# Solar_Charge_Controller_ver2.net
KiCad netlist of a schematic drawn in EAGLE
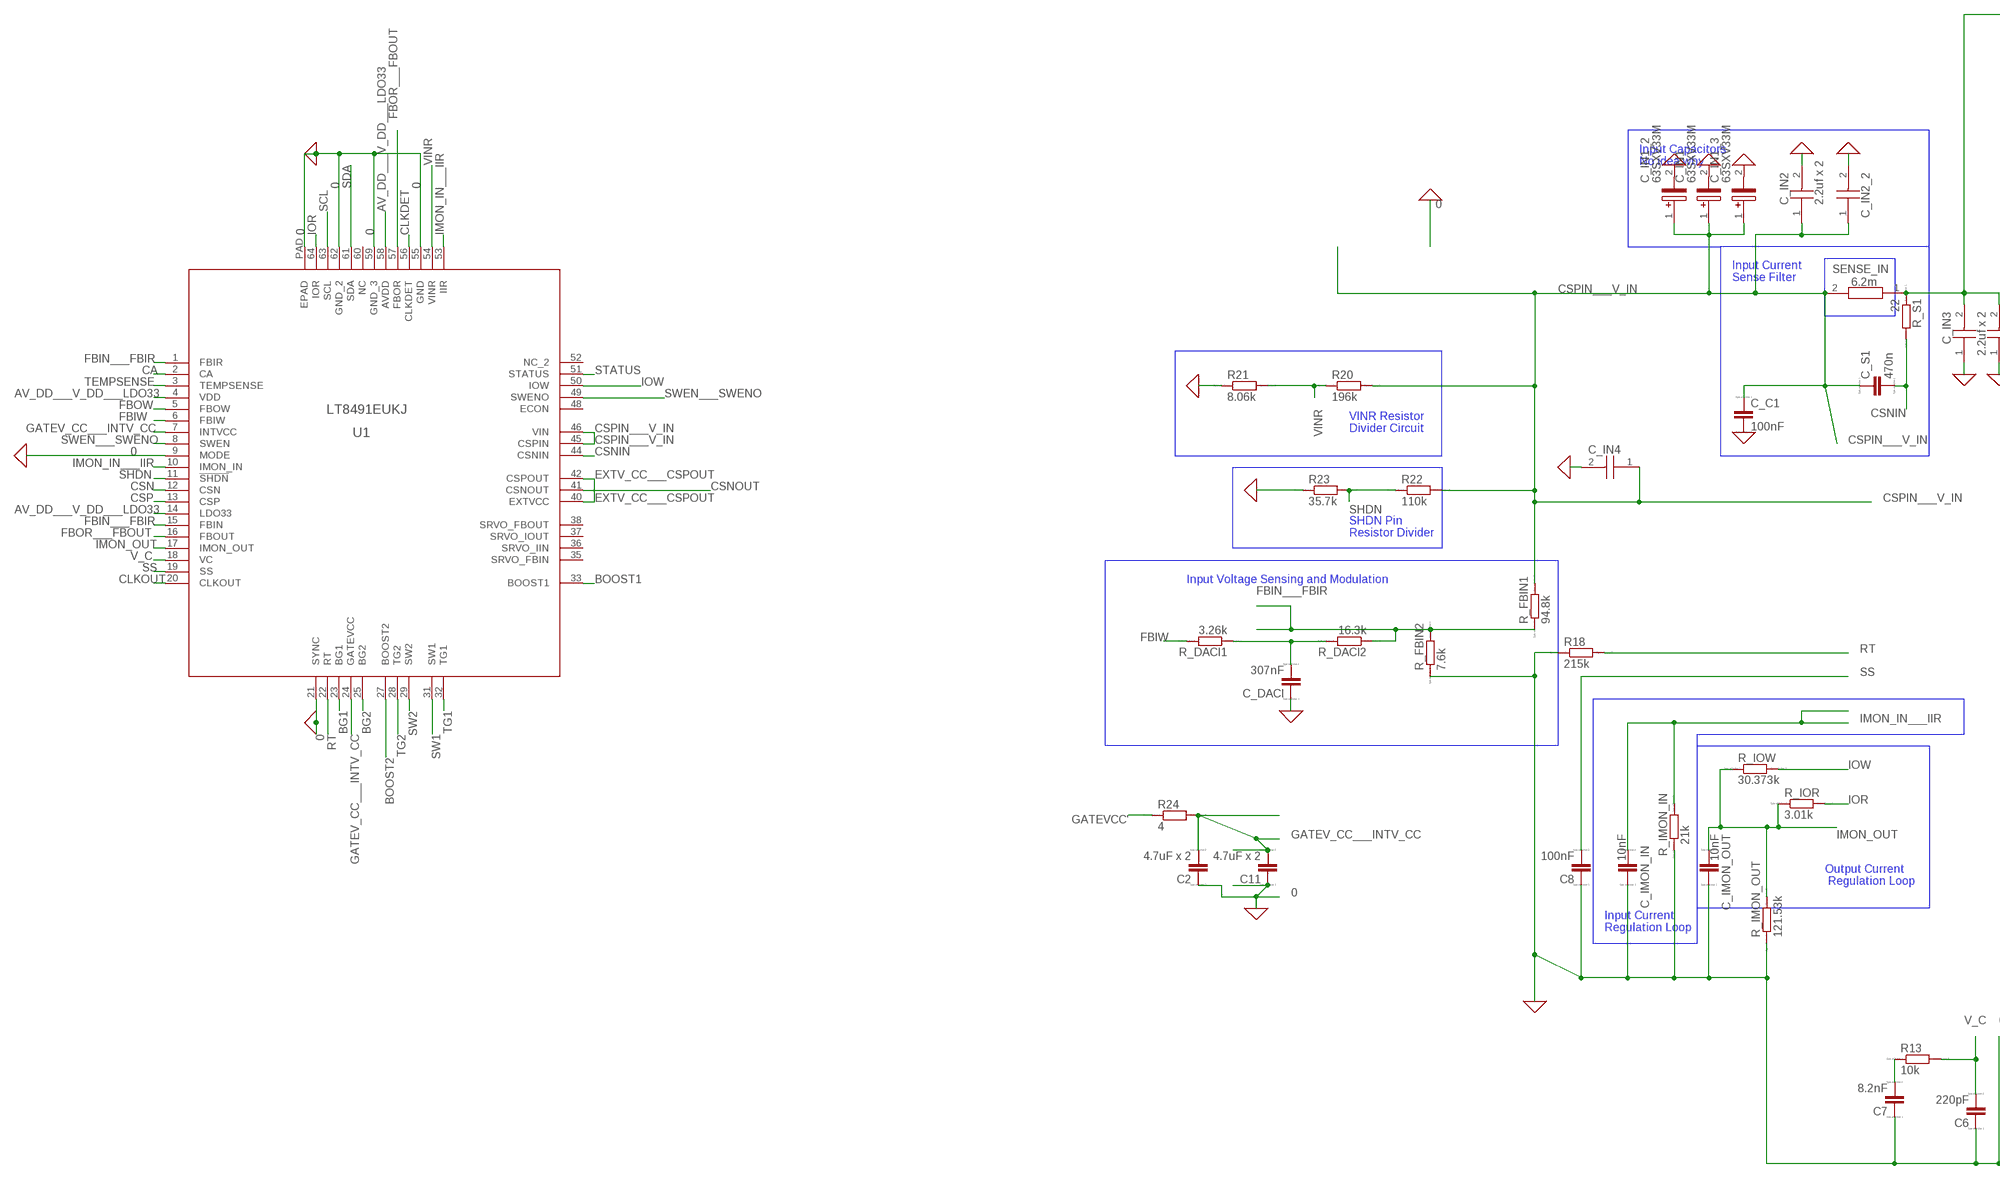
[diagram p0: schematic, sheet 1, part 1 of 2]
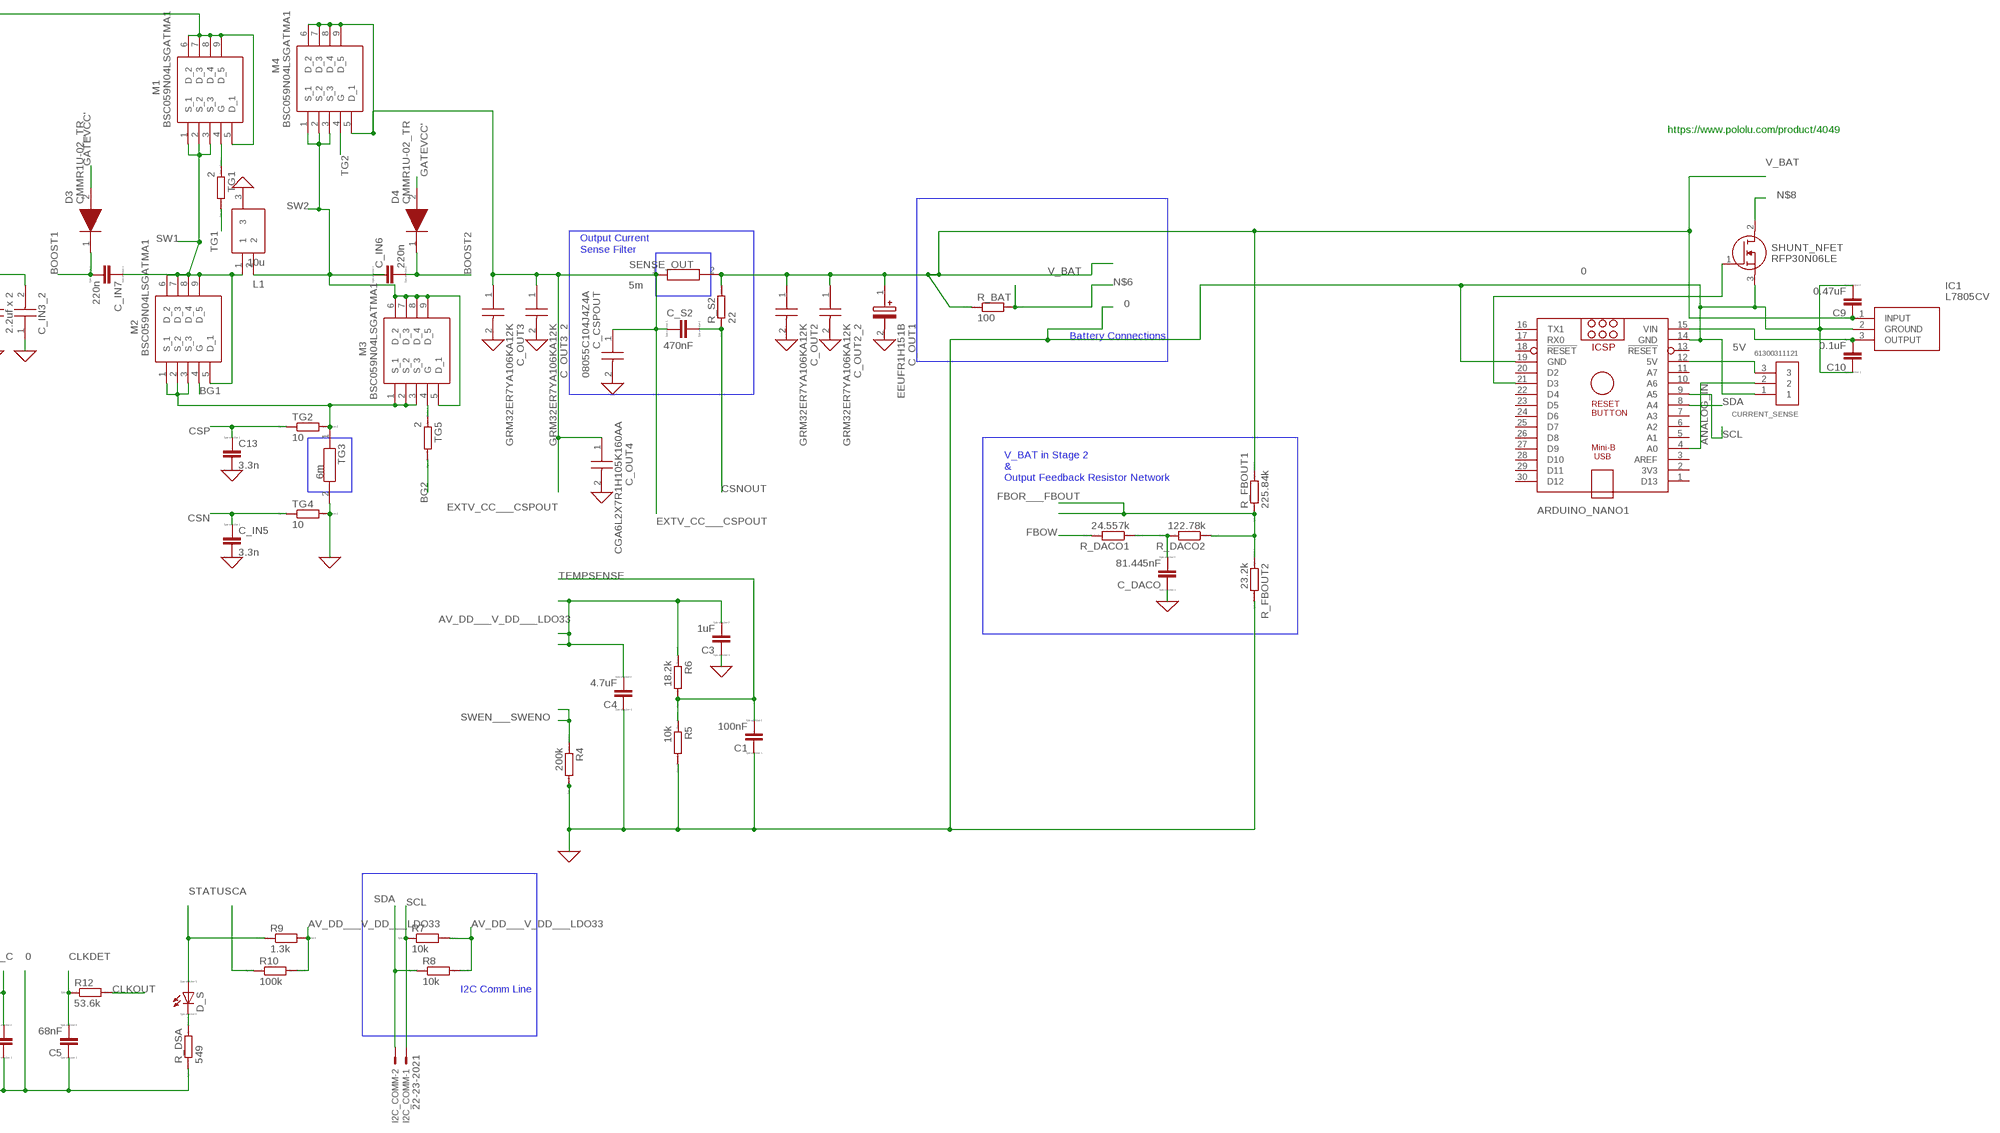
[diagram p1: schematic, sheet 1, part 2 of 2]

(export (version "E")
  (design (tool "Eeschema 10.0.6"))
  (components
    (comp (ref "ARDUINO_NANO1")
      (value "ARDUINO_NANO")
      (footprint "eagle-import:ARDUINO_NANO")
      (libsource (lib "eagle-import") (part "ARDUINO_NANO"))
    )
    (comp (ref "C1")
      (value "100nF")
      (footprint "eagle-import:C1206")
      (libsource (lib "eagle-import") (part "CC1206"))
    )
    (comp (ref "C2")
      (value "4.7uF x 2")
      (footprint "eagle-import:C1206")
      (libsource (lib "eagle-import") (part "CC1206"))
    )
    (comp (ref "C3")
      (value "1uF")
      (footprint "eagle-import:C1206")
      (libsource (lib "eagle-import") (part "CC1206"))
    )
    (comp (ref "C4")
      (value "4.7uF")
      (footprint "eagle-import:C1206")
      (libsource (lib "eagle-import") (part "CC1206"))
    )
    (comp (ref "C5")
      (value "68nF")
      (footprint "eagle-import:C0603")
      (libsource (lib "eagle-import") (part "CC0603"))
    )
    (comp (ref "C6")
      (value "220pF")
      (footprint "eagle-import:C1206")
      (libsource (lib "eagle-import") (part "CC1206"))
    )
    (comp (ref "C7")
      (value "8.2nF")
      (footprint "eagle-import:C1206")
      (libsource (lib "eagle-import") (part "CC1206"))
    )
    (comp (ref "C8")
      (value "100nF")
      (footprint "eagle-import:C1206")
      (libsource (lib "eagle-import") (part "CC1206"))
    )
    (comp (ref "C9")
      (value "0.47uF")
      (footprint "eagle-import:C1206")
      (libsource (lib "eagle-import") (part "CC1206"))
    )
    (comp (ref "C10")
      (value "0.1uF")
      (footprint "eagle-import:C1206")
      (libsource (lib "eagle-import") (part "CC1206"))
    )
    (comp (ref "C11")
      (value "4.7uF x 2")
      (footprint "eagle-import:C1206")
      (libsource (lib "eagle-import") (part "CC1206"))
    )
    (comp (ref "C13")
      (value "3.3n")
      (footprint "eagle-import:C1206")
      (libsource (lib "eagle-import") (part "CC1206"))
    )
    (comp (ref "CURRENT_SENSE")
      (value "61300311121")
      (footprint "eagle-import:61300311121")
      (fields
        (field (name "DIGI_KEY_PART_NUMBER") "732-5316-ND")
        (field (name "MANUFACTURER") "Wurth Electronics Inc.")
        (field (name "CREATED_BY") "PCBLayout.com")
      )
      (libsource (lib "eagle-import") (part "61300311121"))
    )
    (comp (ref "C_C1")
      (value "100nF")
      (footprint "eagle-import:C1206")
      (libsource (lib "eagle-import") (part "CC1206"))
    )
    (comp (ref "C_CSPOUT")
      (value "08055C104J4Z4A")
      (footprint "eagle-import:CAPC2012X127N")
      (fields (field (name "MOUSER_PART_NUMBER") "581-08055C104J4Z4A"))
      (libsource (lib "eagle-import") (part "08055C104J4Z4A"))
    )
    (comp (ref "C_DACI")
      (value "307nF")
      (footprint "eagle-import:C1206")
      (libsource (lib "eagle-import") (part "CC1206"))
    )
    (comp (ref "C_DACO")
      (value "81.445nF")
      (footprint "eagle-import:C1206")
      (libsource (lib "eagle-import") (part "CC1206"))
    )
    (comp (ref "C_IMON_IN")
      (value "10nF")
      (footprint "eagle-import:C1206")
      (libsource (lib "eagle-import") (part "CC1206"))
    )
    (comp (ref "C_IMON_OUT")
      (value "10nF")
      (footprint "eagle-import:C1206")
      (libsource (lib "eagle-import") (part "CC1206"))
    )
    (comp (ref "C_IN1")
      (value "63SXV33M")
      (footprint "eagle-import:CAPAE830X1200N")
      (fields (field (name "MOUSER_PART_NUMBER") "667-63SXV33M"))
      (libsource (lib "eagle-import") (part "63SXV33M"))
    )
    (comp (ref "C_IN1_2")
      (value "63SXV33M")
      (footprint "eagle-import:CAPAE830X1200N")
      (fields (field (name "MOUSER_PART_NUMBER") "667-63SXV33M"))
      (libsource (lib "eagle-import") (part "63SXV33M"))
    )
    (comp (ref "C_IN1_3")
      (value "63SXV33M")
      (footprint "eagle-import:CAPAE830X1200N")
      (fields (field (name "MOUSER_PART_NUMBER") "667-63SXV33M"))
      (libsource (lib "eagle-import") (part "63SXV33M"))
    )
    (comp (ref "C_IN2")
      (value "2.2uf x 2")
      (footprint "eagle-import:CAPC3325X279N")
      (fields
        (field (name "ARROW_PART_NUMBER") "12101C225KAT2A")
        (field (name "MOUSER_PART_NUMBER") "581-12101C225KAT2A")
      )
      (libsource (lib "eagle-import") (part "12101C225KAT2A"))
    )
    (comp (ref "C_IN2_2")
      (value "2.2uf x 2")
      (footprint "eagle-import:CAPC3325X279N")
      (fields
        (field (name "ARROW_PART_NUMBER") "12101C225KAT2A")
        (field (name "MOUSER_PART_NUMBER") "581-12101C225KAT2A")
      )
      (libsource (lib "eagle-import") (part "12101C225KAT2A"))
    )
    (comp (ref "C_IN3")
      (value "2.2uf x 2")
      (footprint "eagle-import:CAPC3325X279N")
      (fields
        (field (name "ARROW_PART_NUMBER") "12101C225KAT2A")
        (field (name "MOUSER_PART_NUMBER") "581-12101C225KAT2A")
      )
      (libsource (lib "eagle-import") (part "12101C225KAT2A"))
    )
    (comp (ref "C_IN3_2")
      (value "2.2uf x 2")
      (footprint "eagle-import:CAPC3325X279N")
      (fields
        (field (name "ARROW_PART_NUMBER") "12101C225KAT2A")
        (field (name "MOUSER_PART_NUMBER") "581-12101C225KAT2A")
      )
      (libsource (lib "eagle-import") (part "12101C225KAT2A"))
    )
    (comp (ref "C_IN4")
      (value "2.2uf")
      (footprint "eagle-import:CAPC3325X279N")
      (fields
        (field (name "ARROW_PART_NUMBER") "12101C225KAT2A")
        (field (name "MOUSER_PART_NUMBER") "581-12101C225KAT2A")
      )
      (libsource (lib "eagle-import") (part "12101C225KAT2A"))
    )
    (comp (ref "C_IN5")
      (value "3.3n")
      (footprint "eagle-import:C1206")
      (libsource (lib "eagle-import") (part "CC1206"))
    )
    (comp (ref "C_IN6")
      (value "220n")
      (footprint "eagle-import:C1206")
      (libsource (lib "eagle-import") (part "CC1206"))
    )
    (comp (ref "C_IN7")
      (value "220n")
      (footprint "eagle-import:C1206")
      (libsource (lib "eagle-import") (part "CC1206"))
    )
    (comp (ref "C_OUT1")
      (value "EEUFR1H151B")
      (footprint "eagle-import:CAPPRD500W65D1000H1400")
      (libsource (lib "eagle-import") (part "EEUFR1H151B"))
    )
    (comp (ref "C_OUT2")
      (value "GRM32ER7YA106KA12K")
      (footprint "eagle-import:CAPC3225X270N")
      (fields (field (name "MOUSER_PART_NUMBER") "81-GRM32ER7YA106KA2K"))
      (libsource (lib "eagle-import") (part "GRM32ER7YA106KA12K"))
    )
    (comp (ref "C_OUT2_2")
      (value "GRM32ER7YA106KA12K")
      (footprint "eagle-import:CAPC3225X270N")
      (fields (field (name "MOUSER_PART_NUMBER") "81-GRM32ER7YA106KA2K"))
      (libsource (lib "eagle-import") (part "GRM32ER7YA106KA12K"))
    )
    (comp (ref "C_OUT3")
      (value "GRM32ER7YA106KA12K")
      (footprint "eagle-import:CAPC3225X270N")
      (fields (field (name "MOUSER_PART_NUMBER") "81-GRM32ER7YA106KA2K"))
      (libsource (lib "eagle-import") (part "GRM32ER7YA106KA12K"))
    )
    (comp (ref "C_OUT3_2")
      (value "GRM32ER7YA106KA12K")
      (footprint "eagle-import:CAPC3225X270N")
      (fields (field (name "MOUSER_PART_NUMBER") "81-GRM32ER7YA106KA2K"))
      (libsource (lib "eagle-import") (part "GRM32ER7YA106KA12K"))
    )
    (comp (ref "C_OUT4")
      (value "CGA6L2X7R1H105K160AA")
      (footprint "eagle-import:CAPC3225X280N")
      (fields (field (name "MOUSER_PART_NUMBER") "810-CGA6L2X7R1H105K"))
      (libsource (lib "eagle-import") (part "CGA6L2X7R1H105K160AA"))
    )
    (comp (ref "C_S1")
      (value "470n")
      (footprint "eagle-import:C1206")
      (libsource (lib "eagle-import") (part "CC1206"))
    )
    (comp (ref "C_S2")
      (value "470nF")
      (footprint "eagle-import:C1206")
      (libsource (lib "eagle-import") (part "CC1206"))
    )
    (comp (ref "D3")
      (value "CMMR1U-02_TR")
      (footprint "eagle-import:SODFL3818X108N")
      (fields
        (field (name "MANUFACTURER_PART_NUMBER") "CMMR1U-02 TR")
        (field (name "MOUSER_PART_NUMBER") "610-CMMR1U-02")
      )
      (libsource (lib "eagle-import") (part "CMMR1U-02_TR"))
    )
    (comp (ref "D4")
      (value "CMMR1U-02_TR")
      (footprint "eagle-import:SODFL3818X108N")
      (fields
        (field (name "MANUFACTURER_PART_NUMBER") "CMMR1U-02 TR")
        (field (name "MOUSER_PART_NUMBER") "610-CMMR1U-02")
      )
      (libsource (lib "eagle-import") (part "CMMR1U-02_TR"))
    )
    (comp (ref "D_S")
      (value "LED_E")
      (footprint "eagle-import:LED_1206")
      (libsource (lib "eagle-import") (part "LED_E"))
    )
    (comp (ref "I2C_COMM")
      (value "22-23-2021")
      (footprint "eagle-import:22-23-2021")
      (fields (field (name "MF") "MOLEX"))
      (libsource (lib "eagle-import") (part "22-23-2021"))
    )
    (comp (ref "IC1")
      (value "L7805CV")
      (footprint "eagle-import:TO255P460X1020X2008-3P")
      (fields (field (name "MOUSER_PART_NUMBER") "511-L7805CV"))
      (libsource (lib "eagle-import") (part "L7805CV"))
    )
    (comp (ref "L1")
      (value "10u")
      (footprint "eagle-import:SER2900")
      (fields
        (field (name "MANUFACTURER_PART_NUMBER") "SER2915H-103KL")
        (field (name "MOUSER_PART_NUMBER") "994-SER2915H-103KL")
      )
      (libsource (lib "eagle-import") (part "SER2915H-103KL"))
    )
    (comp (ref "M1")
      (value "BSC059N04LSGATMA1")
      (footprint "eagle-import:BSC080N03LSG")
      (fields (field (name "MOUSER_PART_NUMBER") "726-BSC059N04LSGATMA"))
      (libsource (lib "eagle-import") (part "BSC059N04LSGATMA1"))
    )
    (comp (ref "M2")
      (value "BSC059N04LSGATMA1")
      (footprint "eagle-import:BSC080N03LSG")
      (fields (field (name "MOUSER_PART_NUMBER") "726-BSC059N04LSGATMA"))
      (libsource (lib "eagle-import") (part "BSC059N04LSGATMA1"))
    )
    (comp (ref "M3")
      (value "BSC059N04LSGATMA1")
      (footprint "eagle-import:BSC080N03LSG")
      (fields (field (name "MOUSER_PART_NUMBER") "726-BSC059N04LSGATMA"))
      (libsource (lib "eagle-import") (part "BSC059N04LSGATMA1"))
    )
    (comp (ref "M4")
      (value "BSC059N04LSGATMA1")
      (footprint "eagle-import:BSC080N03LSG")
      (fields (field (name "MOUSER_PART_NUMBER") "726-BSC059N04LSGATMA"))
      (libsource (lib "eagle-import") (part "BSC059N04LSGATMA1"))
    )
    (comp (ref "R4")
      (value "200k")
      (footprint "eagle-import:R1206")
      (libsource (lib "eagle-import") (part "RR1206"))
    )
    (comp (ref "R5")
      (value "10k")
      (footprint "eagle-import:R1206")
      (libsource (lib "eagle-import") (part "RR1206"))
    )
    (comp (ref "R6")
      (value "18.2k")
      (footprint "eagle-import:R1206")
      (libsource (lib "eagle-import") (part "RR1206"))
    )
    (comp (ref "R7")
      (value "10k")
      (footprint "eagle-import:R1206")
      (libsource (lib "eagle-import") (part "RR1206"))
    )
    (comp (ref "R8")
      (value "10k")
      (footprint "eagle-import:R1206")
      (libsource (lib "eagle-import") (part "RR1206"))
    )
    (comp (ref "R9")
      (value "1.3k")
      (footprint "eagle-import:R1206")
      (libsource (lib "eagle-import") (part "RR1206"))
    )
    (comp (ref "R10")
      (value "100k")
      (footprint "eagle-import:R1206")
      (libsource (lib "eagle-import") (part "RR1206"))
    )
    (comp (ref "R12")
      (value "53.6k")
      (footprint "eagle-import:R1206")
      (libsource (lib "eagle-import") (part "RR1206"))
    )
    (comp (ref "R13")
      (value "10k")
      (footprint "eagle-import:R1206")
      (libsource (lib "eagle-import") (part "RR1206"))
    )
    (comp (ref "R18")
      (value "215k")
      (footprint "eagle-import:R1206")
      (libsource (lib "eagle-import") (part "RR1206"))
    )
    (comp (ref "R20")
      (value "196k")
      (footprint "eagle-import:R1206")
      (libsource (lib "eagle-import") (part "RR1206"))
    )
    (comp (ref "R21")
      (value "8.06k")
      (footprint "eagle-import:R1206")
      (libsource (lib "eagle-import") (part "RR1206"))
    )
    (comp (ref "R22")
      (value "110k")
      (footprint "eagle-import:R1206")
      (libsource (lib "eagle-import") (part "RR1206"))
    )
    (comp (ref "R23")
      (value "35.7k")
      (footprint "eagle-import:R1206")
      (libsource (lib "eagle-import") (part "RR1206"))
    )
    (comp (ref "R24")
      (value "4")
      (footprint "eagle-import:R1206")
      (libsource (lib "eagle-import") (part "RR1206"))
    )
    (comp (ref "R_BAT")
      (value "100")
      (footprint "eagle-import:R1206")
      (libsource (lib "eagle-import") (part "RR1206"))
    )
    (comp (ref "R_DACI1")
      (value "3.26k")
      (footprint "eagle-import:R1206")
      (libsource (lib "eagle-import") (part "RR1206"))
    )
    (comp (ref "R_DACI2")
      (value "16.3k")
      (footprint "eagle-import:R1206")
      (libsource (lib "eagle-import") (part "RR1206"))
    )
    (comp (ref "R_DACO1")
      (value "24.557k")
      (footprint "eagle-import:R1206")
      (libsource (lib "eagle-import") (part "RR1206"))
    )
    (comp (ref "R_DACO2")
      (value "122.78k")
      (footprint "eagle-import:R1206")
      (libsource (lib "eagle-import") (part "RR1206"))
    )
    (comp (ref "R_DSA")
      (value "549")
      (footprint "eagle-import:R1206")
      (libsource (lib "eagle-import") (part "RR1206"))
    )
    (comp (ref "R_FBIN1")
      (value "94.8k")
      (footprint "eagle-import:R1206")
      (libsource (lib "eagle-import") (part "RR1206"))
    )
    (comp (ref "R_FBIN2")
      (value "7.6k")
      (footprint "eagle-import:R1206")
      (libsource (lib "eagle-import") (part "RR1206"))
    )
    (comp (ref "R_FBOUT1")
      (value "225.84k")
      (footprint "eagle-import:R1206")
      (libsource (lib "eagle-import") (part "RR1206"))
    )
    (comp (ref "R_FBOUT2")
      (value "23.2k")
      (footprint "eagle-import:R1206")
      (libsource (lib "eagle-import") (part "RR1206"))
    )
    (comp (ref "R_IMON_IN")
      (value "21k")
      (footprint "eagle-import:R1206")
      (libsource (lib "eagle-import") (part "RR1206"))
    )
    (comp (ref "R_IMON_OUT")
      (value "121.53k")
      (footprint "eagle-import:R1206")
      (libsource (lib "eagle-import") (part "RR1206"))
    )
    (comp (ref "R_IOR")
      (value "3.01k")
      (footprint "eagle-import:R1206")
      (libsource (lib "eagle-import") (part "RR1206"))
    )
    (comp (ref "R_IOW")
      (value "30.373k")
      (footprint "eagle-import:R1206")
      (libsource (lib "eagle-import") (part "RR1206"))
    )
    (comp (ref "R_S1")
      (value "22")
      (footprint "eagle-import:R1206")
      (libsource (lib "eagle-import") (part "RR1206"))
    )
    (comp (ref "R_S2")
      (value "22")
      (footprint "eagle-import:R1206")
      (libsource (lib "eagle-import") (part "RR1206"))
    )
    (comp (ref "SENSE_IN")
      (value "6.2m")
      (footprint "eagle-import:RESC2012X80N")
      (fields (field (name "MANUFACTURER_PART_NUMBER") "ERJ6LWFR006V"))
      (libsource (lib "eagle-import") (part "ERJ6LWFR006V"))
    )
    (comp (ref "SENSE_OUT")
      (value "5m")
      (footprint "eagle-import:RESC3216X89N")
      (fields
        (field (name "MANUFACTURER_PART_NUMBER") "ERJ-MP2MF5M0U")
        (field (name "MOUSER_PART_NUMBER") "667-ERJ-MP2MF5M0U")
      )
      (libsource (lib "eagle-import") (part "ERJ-MP2MF5M0U"))
    )
    (comp (ref "SHUNT_NFET")
      (value "RFP30N06LE")
      (footprint "eagle-import:TO254P470X1016X2019-3P")
      (fields (field (name "MOUSER_PART_NUMBER") "512-RFP30N06LE"))
      (libsource (lib "eagle-import") (part "RFP30N06LE"))
    )
    (comp (ref "TG1")
      (value "2")
      (footprint "eagle-import:R1206")
      (libsource (lib "eagle-import") (part "RR1206"))
    )
    (comp (ref "TG2")
      (value "10")
      (footprint "eagle-import:R1206")
      (libsource (lib "eagle-import") (part "RR1206"))
    )
    (comp (ref "TG3")
      (value "6m")
      (footprint "eagle-import:RESC2012X80N")
      (fields (field (name "MANUFACTURER_PART_NUMBER") "ERJ6LWFR006V"))
      (libsource (lib "eagle-import") (part "ERJ6LWFR006V"))
    )
    (comp (ref "TG4")
      (value "10")
      (footprint "eagle-import:R1206")
      (libsource (lib "eagle-import") (part "RR1206"))
    )
    (comp (ref "TG5")
      (value "2")
      (footprint "eagle-import:R1206")
      (libsource (lib "eagle-import") (part "RR1206"))
    )
    (comp (ref "U1")
      (value "LT8491EUKJ")
      (footprint "eagle-import:QFN64(58)-UKJ-REV0_ADI")
      (fields (field (name "COPYRIGHT") "Copyright (C) 2018 Accelerated Designs. All rights reserved"))
      (libsource (lib "eagle-import") (part "LT8491EUKJ"))
    )
  )
  (nets
    (net (code "1") (name "/5V") (class "Default")
      (node (ref "ARDUINO_NANO1") (pin "12") (pinfunction "5V_12") (pintype "power_in"))
      (node (ref "CURRENT_SENSE") (pin "3") (pinfunction "3_3") (pintype "passive"))
    )
    (net (code "2") (name "/ANALOG_IN") (class "Default")
      (node (ref "ARDUINO_NANO1") (pin "4") (pinfunction "A0_4") (pintype "bidirectional"))
      (node (ref "CURRENT_SENSE") (pin "2") (pinfunction "2_2") (pintype "passive"))
    )
    (net (code "3") (name "/AV_DD___V_DD___LDO33") (class "Default")
      (node (ref "C3") (pin "2") (pinfunction "2_2") (pintype "passive"))
      (node (ref "C4") (pin "2") (pinfunction "2_2") (pintype "passive"))
      (node (ref "R10") (pin "2") (pinfunction "2_2") (pintype "passive"))
      (node (ref "R6") (pin "1") (pinfunction "1_1") (pintype "passive"))
      (node (ref "R7") (pin "2") (pinfunction "2_2") (pintype "passive"))
      (node (ref "R8") (pin "2") (pinfunction "2_2") (pintype "passive"))
      (node (ref "R9") (pin "2") (pinfunction "2_2") (pintype "passive"))
      (node (ref "U1") (pin "14") (pinfunction "LDO33_14") (pintype "passive"))
      (node (ref "U1") (pin "4") (pinfunction "VDD_4") (pintype "passive"))
      (node (ref "U1") (pin "58") (pinfunction "AVDD_58") (pintype "passive"))
    )
    (net (code "4") (name "/BG1") (class "Default")
      (node (ref "M2") (pin "4") (pinfunction "G_4") (pintype "bidirectional"))
      (node (ref "U1") (pin "23") (pinfunction "BG1_23") (pintype "passive"))
    )
    (net (code "5") (name "/BG2") (class "Default")
      (node (ref "TG5") (pin "2") (pinfunction "2_2") (pintype "passive"))
      (node (ref "U1") (pin "25") (pinfunction "BG2_25") (pintype "passive"))
    )
    (net (code "6") (name "/BOOST1") (class "Default")
      (node (ref "C_IN7") (pin "2") (pinfunction "2_2") (pintype "passive"))
      (node (ref "D3") (pin "1") (pinfunction "K_1") (pintype "bidirectional"))
      (node (ref "U1") (pin "33") (pinfunction "BOOST1_33") (pintype "passive"))
    )
    (net (code "7") (name "/BOOST2") (class "Default")
      (node (ref "C_IN6") (pin "2") (pinfunction "2_2") (pintype "passive"))
      (node (ref "D4") (pin "1") (pinfunction "K_1") (pintype "bidirectional"))
      (node (ref "U1") (pin "27") (pinfunction "BOOST2_27") (pintype "passive"))
    )
    (net (code "8") (name "/CA") (class "Default")
      (node (ref "R10") (pin "1") (pinfunction "1_1") (pintype "passive"))
      (node (ref "U1") (pin "2") (pinfunction "CA_2") (pintype "passive"))
    )
    (net (code "9") (name "/CLKDET") (class "Default")
      (node (ref "C5") (pin "2") (pinfunction "2_2") (pintype "passive"))
      (node (ref "R12") (pin "1") (pinfunction "1_1") (pintype "passive"))
      (node (ref "U1") (pin "56") (pinfunction "CLKDET_56") (pintype "passive"))
    )
    (net (code "10") (name "/CLKOUT") (class "Default")
      (node (ref "R12") (pin "2") (pinfunction "2_2") (pintype "passive"))
      (node (ref "U1") (pin "20") (pinfunction "CLKOUT_20") (pintype "passive"))
    )
    (net (code "11") (name "/CSN") (class "Default")
      (node (ref "C_IN5") (pin "1") (pinfunction "1_1") (pintype "passive"))
      (node (ref "TG4") (pin "1") (pinfunction "1_1") (pintype "passive"))
      (node (ref "U1") (pin "12") (pinfunction "CSN_12") (pintype "passive"))
    )
    (net (code "12") (name "/CSNIN") (class "Default")
      (node (ref "C_S1") (pin "2") (pinfunction "2_2") (pintype "passive"))
      (node (ref "R_S1") (pin "2") (pinfunction "2_2") (pintype "passive"))
      (node (ref "U1") (pin "44") (pinfunction "CSNIN_44") (pintype "passive"))
    )
    (net (code "13") (name "/CSNOUT") (class "Default")
      (node (ref "C_S2") (pin "2") (pinfunction "2_2") (pintype "passive"))
      (node (ref "R_S2") (pin "1") (pinfunction "1_1") (pintype "passive"))
      (node (ref "U1") (pin "41") (pinfunction "CSNOUT_41") (pintype "passive"))
    )
    (net (code "14") (name "/CSP") (class "Default")
      (node (ref "C13") (pin "1") (pinfunction "1_1") (pintype "passive"))
      (node (ref "TG2") (pin "1") (pinfunction "1_1") (pintype "passive"))
      (node (ref "U1") (pin "13") (pinfunction "CSP_13") (pintype "passive"))
    )
    (net (code "15") (name "/CSPIN___V_IN") (class "Default")
      (node (ref "C_C1") (pin "1") (pinfunction "1_1") (pintype "passive"))
      (node (ref "C_IN1") (pin "1") (pinfunction "+_1") (pintype "bidirectional"))
      (node (ref "C_IN1_2") (pin "1") (pinfunction "+_1") (pintype "bidirectional"))
      (node (ref "C_IN1_3") (pin "1") (pinfunction "+_1") (pintype "bidirectional"))
      (node (ref "C_IN2") (pin "1") (pinfunction "1_1") (pintype "bidirectional"))
      (node (ref "C_IN2_2") (pin "1") (pinfunction "1_1") (pintype "bidirectional"))
      (node (ref "C_IN4") (pin "1") (pinfunction "1_1") (pintype "bidirectional"))
      (node (ref "C_S1") (pin "1") (pinfunction "1_1") (pintype "passive"))
      (node (ref "R20") (pin "2") (pinfunction "2_2") (pintype "passive"))
      (node (ref "R22") (pin "2") (pinfunction "2_2") (pintype "passive"))
      (node (ref "R_FBIN1") (pin "2") (pinfunction "2_2") (pintype "passive"))
      (node (ref "SENSE_IN") (pin "2") (pinfunction "2_2") (pintype "bidirectional"))
      (node (ref "U1") (pin "45") (pinfunction "CSPIN_45") (pintype "passive"))
      (node (ref "U1") (pin "46") (pinfunction "VIN_46") (pintype "passive"))
    )
    (net (code "16") (name "/EXTV_CC___CSPOUT") (class "Default")
      (node (ref "C_CSPOUT") (pin "1") (pinfunction "1_1") (pintype "bidirectional"))
      (node (ref "C_OUT3") (pin "1") (pinfunction "1_1") (pintype "bidirectional"))
      (node (ref "C_OUT3_2") (pin "1") (pinfunction "1_1") (pintype "bidirectional"))
      (node (ref "C_OUT4") (pin "1") (pinfunction "1_1") (pintype "bidirectional"))
      (node (ref "C_S2") (pin "1") (pinfunction "1_1") (pintype "passive"))
      (node (ref "M4") (pin "5") (pinfunction "D_1_5") (pintype "bidirectional"))
      (node (ref "M4") (pin "6") (pinfunction "D_2_6") (pintype "bidirectional"))
      (node (ref "M4") (pin "7") (pinfunction "D_3_7") (pintype "bidirectional"))
      (node (ref "M4") (pin "8") (pinfunction "D_4_8") (pintype "bidirectional"))
      (node (ref "M4") (pin "9") (pinfunction "D_5_9") (pintype "bidirectional"))
      (node (ref "SENSE_OUT") (pin "1") (pinfunction "1_1") (pintype "bidirectional"))
      (node (ref "U1") (pin "40") (pinfunction "EXTVCC_40") (pintype "passive"))
      (node (ref "U1") (pin "42") (pinfunction "CSPOUT_42") (pintype "passive"))
    )
    (net (code "17") (name "/FBIN___FBIR") (class "Default")
      (node (ref "R_DACI2") (pin "1") (pinfunction "1_1") (pintype "passive"))
      (node (ref "R_FBIN1") (pin "1") (pinfunction "1_1") (pintype "passive"))
      (node (ref "R_FBIN2") (pin "2") (pinfunction "2_2") (pintype "passive"))
      (node (ref "U1") (pin "1") (pinfunction "FBIR_1") (pintype "passive"))
      (node (ref "U1") (pin "15") (pinfunction "FBIN_15") (pintype "passive"))
    )
    (net (code "18") (name "/FBIW") (class "Default")
      (node (ref "R_DACI1") (pin "2") (pinfunction "2_2") (pintype "passive"))
      (node (ref "U1") (pin "6") (pinfunction "FBIW_6") (pintype "passive"))
    )
    (net (code "19") (name "/FBOR___FBOUT") (class "Default")
      (node (ref "R_DACO2") (pin "1") (pinfunction "1_1") (pintype "passive"))
      (node (ref "R_FBOUT1") (pin "1") (pinfunction "1_1") (pintype "passive"))
      (node (ref "R_FBOUT2") (pin "1") (pinfunction "1_1") (pintype "passive"))
      (node (ref "U1") (pin "16") (pinfunction "FBOUT_16") (pintype "passive"))
      (node (ref "U1") (pin "57") (pinfunction "FBOR_57") (pintype "passive"))
    )
    (net (code "20") (name "/FBOW") (class "Default")
      (node (ref "R_DACO1") (pin "2") (pinfunction "2_2") (pintype "passive"))
      (node (ref "U1") (pin "5") (pinfunction "FBOW_5") (pintype "passive"))
    )
    (net (code "21") (name "/GATEVCC'") (class "Default")
      (node (ref "D3") (pin "2") (pinfunction "A_2") (pintype "bidirectional"))
      (node (ref "D4") (pin "2") (pinfunction "A_2") (pintype "bidirectional"))
      (node (ref "R24") (pin "1") (pinfunction "1_1") (pintype "passive"))
    )
    (net (code "22") (name "/GATEV_CC___INTV_CC") (class "Default")
      (node (ref "C11") (pin "2") (pinfunction "2_2") (pintype "passive"))
      (node (ref "C2") (pin "2") (pinfunction "2_2") (pintype "passive"))
      (node (ref "R24") (pin "2") (pinfunction "2_2") (pintype "passive"))
      (node (ref "U1") (pin "24") (pinfunction "GATEVCC_24") (pintype "passive"))
      (node (ref "U1") (pin "7") (pinfunction "INTVCC_7") (pintype "passive"))
    )
    (net (code "23") (name "/IMON_IN___IIR") (class "Default")
      (node (ref "C_IMON_IN") (pin "2") (pinfunction "2_2") (pintype "passive"))
      (node (ref "R_IMON_IN") (pin "2") (pinfunction "2_2") (pintype "passive"))
      (node (ref "U1") (pin "10") (pinfunction "IMON_IN_10") (pintype "passive"))
      (node (ref "U1") (pin "53") (pinfunction "IIR_53") (pintype "passive"))
    )
    (net (code "24") (name "/IMON_OUT") (class "Default")
      (node (ref "C_IMON_OUT") (pin "2") (pinfunction "2_2") (pintype "passive"))
      (node (ref "R_IMON_OUT") (pin "2") (pinfunction "2_2") (pintype "passive"))
      (node (ref "R_IOR") (pin "1") (pinfunction "1_1") (pintype "passive"))
      (node (ref "R_IOW") (pin "1") (pinfunction "1_1") (pintype "passive"))
      (node (ref "U1") (pin "17") (pinfunction "IMON_OUT_17") (pintype "passive"))
    )
    (net (code "25") (name "/IOR") (class "Default")
      (node (ref "R_IOR") (pin "2") (pinfunction "2_2") (pintype "passive"))
      (node (ref "U1") (pin "64") (pinfunction "IOR_64") (pintype "passive"))
    )
    (net (code "26") (name "/IOW") (class "Default")
      (node (ref "R_IOW") (pin "2") (pinfunction "2_2") (pintype "passive"))
      (node (ref "U1") (pin "50") (pinfunction "IOW_50") (pintype "passive"))
    )
    (net (code "27") (name "/N$6") (class "Default")
      (node (ref "R_BAT") (pin "2") (pinfunction "2_2") (pintype "passive"))
    )
    (net (code "28") (name "/N$8") (class "Default")
      (node (ref "SHUNT_NFET") (pin "2") (pinfunction "D_2") (pintype "bidirectional"))
    )
    (net (code "29") (name "/RT") (class "Default")
      (node (ref "R18") (pin "2") (pinfunction "2_2") (pintype "passive"))
      (node (ref "U1") (pin "22") (pinfunction "RT_22") (pintype "passive"))
    )
    (net (code "30") (name "/SCL") (class "Default")
      (node (ref "ARDUINO_NANO1") (pin "9") (pinfunction "A5_9") (pintype "bidirectional"))
      (node (ref "I2C_COMM") (pin "1") (pinfunction "S_1") (pintype "passive"))
      (node (ref "R7") (pin "1") (pinfunction "1_1") (pintype "passive"))
      (node (ref "U1") (pin "63") (pinfunction "SCL_63") (pintype "passive"))
    )
    (net (code "31") (name "/SDA") (class "Default")
      (node (ref "ARDUINO_NANO1") (pin "8") (pinfunction "A4_8") (pintype "bidirectional"))
      (node (ref "I2C_COMM") (pin "2") (pinfunction "S_2") (pintype "passive"))
      (node (ref "R8") (pin "1") (pinfunction "1_1") (pintype "passive"))
      (node (ref "U1") (pin "61") (pinfunction "SDA_61") (pintype "passive"))
    )
    (net (code "32") (name "/SHDN") (class "Default")
      (node (ref "R22") (pin "1") (pinfunction "1_1") (pintype "passive"))
      (node (ref "R23") (pin "2") (pinfunction "2_2") (pintype "passive"))
      (node (ref "U1") (pin "11") (pinfunction "~{SHDN}_11") (pintype "passive"))
    )
    (net (code "33") (name "/SS") (class "Default")
      (node (ref "C8") (pin "2") (pinfunction "2_2") (pintype "passive"))
      (node (ref "U1") (pin "19") (pinfunction "SS_19") (pintype "passive"))
    )
    (net (code "34") (name "/STATUS") (class "Default")
      (node (ref "D_S") (pin "A") (pinfunction "A_A") (pintype "passive"))
      (node (ref "R9") (pin "1") (pinfunction "1_1") (pintype "passive"))
      (node (ref "U1") (pin "51") (pinfunction "STATUS_51") (pintype "passive"))
    )
    (net (code "35") (name "/SW1") (class "Default")
      (node (ref "C_IN7") (pin "1") (pinfunction "1_1") (pintype "passive"))
      (node (ref "L1") (pin "1") (pinfunction "1_1") (pintype "bidirectional"))
      (node (ref "M1") (pin "1") (pinfunction "S_1_1") (pintype "bidirectional"))
      (node (ref "M1") (pin "2") (pinfunction "S_2_2") (pintype "bidirectional"))
      (node (ref "M1") (pin "3") (pinfunction "S_3_3") (pintype "bidirectional"))
      (node (ref "M2") (pin "5") (pinfunction "D_1_5") (pintype "bidirectional"))
      (node (ref "M2") (pin "6") (pinfunction "D_2_6") (pintype "bidirectional"))
      (node (ref "M2") (pin "7") (pinfunction "D_3_7") (pintype "bidirectional"))
      (node (ref "M2") (pin "8") (pinfunction "D_4_8") (pintype "bidirectional"))
      (node (ref "M2") (pin "9") (pinfunction "D_5_9") (pintype "bidirectional"))
      (node (ref "U1") (pin "31") (pinfunction "SW1_31") (pintype "passive"))
    )
    (net (code "36") (name "/SW2") (class "Default")
      (node (ref "C_IN6") (pin "1") (pinfunction "1_1") (pintype "passive"))
      (node (ref "L1") (pin "2") (pinfunction "2_2") (pintype "bidirectional"))
      (node (ref "M3") (pin "5") (pinfunction "D_1_5") (pintype "bidirectional"))
      (node (ref "M3") (pin "6") (pinfunction "D_2_6") (pintype "bidirectional"))
      (node (ref "M3") (pin "7") (pinfunction "D_3_7") (pintype "bidirectional"))
      (node (ref "M3") (pin "8") (pinfunction "D_4_8") (pintype "bidirectional"))
      (node (ref "M3") (pin "9") (pinfunction "D_5_9") (pintype "bidirectional"))
      (node (ref "M4") (pin "1") (pinfunction "S_1_1") (pintype "bidirectional"))
      (node (ref "M4") (pin "2") (pinfunction "S_2_2") (pintype "bidirectional"))
      (node (ref "M4") (pin "3") (pinfunction "S_3_3") (pintype "bidirectional"))
      (node (ref "U1") (pin "29") (pinfunction "SW2_29") (pintype "passive"))
    )
    (net (code "37") (name "/SWEN___SWENO") (class "Default")
      (node (ref "R4") (pin "1") (pinfunction "1_1") (pintype "passive"))
      (node (ref "U1") (pin "49") (pinfunction "SWENO_49") (pintype "passive"))
      (node (ref "U1") (pin "8") (pinfunction "SWEN_8") (pintype "passive"))
    )
    (net (code "38") (name "/TEMPSENSE") (class "Default")
      (node (ref "C1") (pin "2") (pinfunction "2_2") (pintype "passive"))
      (node (ref "R5") (pin "1") (pinfunction "1_1") (pintype "passive"))
      (node (ref "R6") (pin "2") (pinfunction "2_2") (pintype "passive"))
      (node (ref "U1") (pin "3") (pinfunction "TEMPSENSE_3") (pintype "passive"))
    )
    (net (code "39") (name "/TG1") (class "Default")
      (node (ref "TG1") (pin "2") (pinfunction "2_2") (pintype "passive"))
      (node (ref "U1") (pin "32") (pinfunction "TG1_32") (pintype "passive"))
    )
    (net (code "40") (name "/TG2") (class "Default")
      (node (ref "M4") (pin "4") (pinfunction "G_4") (pintype "bidirectional"))
      (node (ref "U1") (pin "28") (pinfunction "TG2_28") (pintype "passive"))
    )
    (net (code "41") (name "/VINR") (class "Default")
      (node (ref "R20") (pin "1") (pinfunction "1_1") (pintype "passive"))
      (node (ref "R21") (pin "2") (pinfunction "2_2") (pintype "passive"))
      (node (ref "U1") (pin "54") (pinfunction "VINR_54") (pintype "passive"))
    )
    (net (code "42") (name "/V_BAT") (class "Default")
      (node (ref "C9") (pin "1") (pinfunction "1_1") (pintype "passive"))
      (node (ref "C_OUT1") (pin "1") (pinfunction "+_1") (pintype "bidirectional"))
      (node (ref "C_OUT2") (pin "1") (pinfunction "1_1") (pintype "bidirectional"))
      (node (ref "C_OUT2_2") (pin "1") (pinfunction "1_1") (pintype "bidirectional"))
      (node (ref "IC1") (pin "1") (pinfunction "INPUT_1") (pintype "bidirectional"))
      (node (ref "R_BAT") (pin "1") (pinfunction "1_1") (pintype "passive"))
      (node (ref "R_FBOUT1") (pin "2") (pinfunction "2_2") (pintype "passive"))
      (node (ref "R_S2") (pin "2") (pinfunction "2_2") (pintype "passive"))
      (node (ref "SENSE_OUT") (pin "2") (pinfunction "2_2") (pintype "bidirectional"))
    )
    (net (code "43") (name "/V_C") (class "Default")
      (node (ref "C6") (pin "2") (pinfunction "2_2") (pintype "passive"))
      (node (ref "R13") (pin "2") (pinfunction "2_2") (pintype "passive"))
      (node (ref "U1") (pin "18") (pinfunction "VC_18") (pintype "passive"))
    )
    (net (code "44") (name "GND") (class "Default")
      (node (ref "ARDUINO_NANO1") (pin "14") (pinfunction "GND_14") (pintype "power_in"))
      (node (ref "ARDUINO_NANO1") (pin "19") (pinfunction "GND_19") (pintype "power_in"))
      (node (ref "C1") (pin "1") (pinfunction "1_1") (pintype "passive"))
      (node (ref "C10") (pin "1") (pinfunction "1_1") (pintype "passive"))
      (node (ref "C11") (pin "1") (pinfunction "1_1") (pintype "passive"))
      (node (ref "C13") (pin "2") (pinfunction "2_2") (pintype "passive"))
      (node (ref "C2") (pin "1") (pinfunction "1_1") (pintype "passive"))
      (node (ref "C3") (pin "1") (pinfunction "1_1") (pintype "passive"))
      (node (ref "C4") (pin "1") (pinfunction "1_1") (pintype "passive"))
      (node (ref "C5") (pin "1") (pinfunction "1_1") (pintype "passive"))
      (node (ref "C6") (pin "1") (pinfunction "1_1") (pintype "passive"))
      (node (ref "C7") (pin "1") (pinfunction "1_1") (pintype "passive"))
      (node (ref "C8") (pin "1") (pinfunction "1_1") (pintype "passive"))
      (node (ref "C9") (pin "2") (pinfunction "2_2") (pintype "passive"))
      (node (ref "CURRENT_SENSE") (pin "1") (pinfunction "1_1") (pintype "passive"))
      (node (ref "C_C1") (pin "2") (pinfunction "2_2") (pintype "passive"))
      (node (ref "C_CSPOUT") (pin "2") (pinfunction "2_2") (pintype "bidirectional"))
      (node (ref "C_DACI") (pin "1") (pinfunction "1_1") (pintype "passive"))
      (node (ref "C_DACO") (pin "1") (pinfunction "1_1") (pintype "passive"))
      (node (ref "C_IMON_IN") (pin "1") (pinfunction "1_1") (pintype "passive"))
      (node (ref "C_IMON_OUT") (pin "1") (pinfunction "1_1") (pintype "passive"))
      (node (ref "C_IN1") (pin "2") (pinfunction "-_2") (pintype "bidirectional"))
      (node (ref "C_IN1_2") (pin "2") (pinfunction "-_2") (pintype "bidirectional"))
      (node (ref "C_IN1_3") (pin "2") (pinfunction "-_2") (pintype "bidirectional"))
      (node (ref "C_IN2") (pin "2") (pinfunction "2_2") (pintype "bidirectional"))
      (node (ref "C_IN2_2") (pin "2") (pinfunction "2_2") (pintype "bidirectional"))
      (node (ref "C_IN3") (pin "1") (pinfunction "1_1") (pintype "bidirectional"))
      (node (ref "C_IN3_2") (pin "1") (pinfunction "1_1") (pintype "bidirectional"))
      (node (ref "C_IN4") (pin "2") (pinfunction "2_2") (pintype "bidirectional"))
      (node (ref "C_IN5") (pin "2") (pinfunction "2_2") (pintype "passive"))
      (node (ref "C_OUT1") (pin "2") (pinfunction "-_2") (pintype "bidirectional"))
      (node (ref "C_OUT2") (pin "2") (pinfunction "2_2") (pintype "bidirectional"))
      (node (ref "C_OUT2_2") (pin "2") (pinfunction "2_2") (pintype "bidirectional"))
      (node (ref "C_OUT3") (pin "2") (pinfunction "2_2") (pintype "bidirectional"))
      (node (ref "C_OUT3_2") (pin "2") (pinfunction "2_2") (pintype "bidirectional"))
      (node (ref "C_OUT4") (pin "2") (pinfunction "2_2") (pintype "bidirectional"))
      (node (ref "IC1") (pin "2") (pinfunction "GROUND_2") (pintype "bidirectional"))
      (node (ref "L1") (pin "3") (pinfunction "3_3") (pintype "bidirectional"))
      (node (ref "R18") (pin "1") (pinfunction "1_1") (pintype "passive"))
      (node (ref "R21") (pin "1") (pinfunction "1_1") (pintype "passive"))
      (node (ref "R23") (pin "1") (pinfunction "1_1") (pintype "passive"))
      (node (ref "R4") (pin "2") (pinfunction "2_2") (pintype "passive"))
      (node (ref "R5") (pin "2") (pinfunction "2_2") (pintype "passive"))
      (node (ref "R_DSA") (pin "1") (pinfunction "1_1") (pintype "passive"))
      (node (ref "R_FBIN2") (pin "1") (pinfunction "1_1") (pintype "passive"))
      (node (ref "R_FBOUT2") (pin "2") (pinfunction "2_2") (pintype "passive"))
      (node (ref "R_IMON_IN") (pin "1") (pinfunction "1_1") (pintype "passive"))
      (node (ref "R_IMON_OUT") (pin "1") (pinfunction "1_1") (pintype "passive"))
      (node (ref "SHUNT_NFET") (pin "3") (pinfunction "S_3") (pintype "bidirectional"))
      (node (ref "TG3") (pin "2") (pinfunction "2_2") (pintype "bidirectional"))
      (node (ref "TG4") (pin "2") (pinfunction "2_2") (pintype "passive"))
      (node (ref "U1") (pin "21") (pinfunction "SYNC_21") (pintype "passive"))
      (node (ref "U1") (pin "55") (pinfunction "GND_55") (pintype "passive"))
      (node (ref "U1") (pin "59") (pinfunction "GND_3_59") (pintype "passive"))
      (node (ref "U1") (pin "62") (pinfunction "GND_2_62") (pintype "passive"))
      (node (ref "U1") (pin "9") (pinfunction "MODE_9") (pintype "passive"))
      (node (ref "U1") (pin "PAD") (pinfunction "EPAD_PAD") (pintype "passive"))
    )
    (net (code "45") (name "Net-(ARDUINO_NANO1-D3)") (class "Default")
      (node (ref "ARDUINO_NANO1") (pin "21") (pinfunction "D3_21") (pintype "bidirectional"))
      (node (ref "SHUNT_NFET") (pin "1") (pinfunction "G_1") (pintype "bidirectional"))
    )
    (net (code "46") (name "Net-(ARDUINO_NANO1-VIN)") (class "Default")
      (node (ref "ARDUINO_NANO1") (pin "15") (pinfunction "VIN_15") (pintype "power_in"))
      (node (ref "C10") (pin "2") (pinfunction "2_2") (pintype "passive"))
      (node (ref "IC1") (pin "3") (pinfunction "OUTPUT_3") (pintype "bidirectional"))
    )
    (net (code "47") (name "Net-(C7-Pad2)") (class "Default")
      (node (ref "C7") (pin "2") (pinfunction "2_2") (pintype "passive"))
      (node (ref "R13") (pin "1") (pinfunction "1_1") (pintype "passive"))
    )
    (net (code "48") (name "Net-(C_DACI-Pad2)") (class "Default")
      (node (ref "C_DACI") (pin "2") (pinfunction "2_2") (pintype "passive"))
      (node (ref "R_DACI1") (pin "1") (pinfunction "1_1") (pintype "passive"))
      (node (ref "R_DACI2") (pin "2") (pinfunction "2_2") (pintype "passive"))
    )
    (net (code "49") (name "Net-(C_DACO-Pad2)") (class "Default")
      (node (ref "C_DACO") (pin "2") (pinfunction "2_2") (pintype "passive"))
      (node (ref "R_DACO1") (pin "1") (pinfunction "1_1") (pintype "passive"))
      (node (ref "R_DACO2") (pin "2") (pinfunction "2_2") (pintype "passive"))
    )
    (net (code "50") (name "Net-(D_S-PadC)") (class "Default")
      (node (ref "D_S") (pin "C") (pinfunction "C_C") (pintype "passive"))
      (node (ref "R_DSA") (pin "2") (pinfunction "2_2") (pintype "passive"))
    )
    (net (code "51") (name "Net-(M1-D_1)") (class "Default")
      (node (ref "C_IN3") (pin "2") (pinfunction "2_2") (pintype "bidirectional"))
      (node (ref "C_IN3_2") (pin "2") (pinfunction "2_2") (pintype "bidirectional"))
      (node (ref "M1") (pin "5") (pinfunction "D_1_5") (pintype "bidirectional"))
      (node (ref "M1") (pin "6") (pinfunction "D_2_6") (pintype "bidirectional"))
      (node (ref "M1") (pin "7") (pinfunction "D_3_7") (pintype "bidirectional"))
      (node (ref "M1") (pin "8") (pinfunction "D_4_8") (pintype "bidirectional"))
      (node (ref "M1") (pin "9") (pinfunction "D_5_9") (pintype "bidirectional"))
      (node (ref "R_S1") (pin "1") (pinfunction "1_1") (pintype "passive"))
      (node (ref "SENSE_IN") (pin "1") (pinfunction "1_1") (pintype "bidirectional"))
    )
    (net (code "52") (name "Net-(M1-G)") (class "Default")
      (node (ref "M1") (pin "4") (pinfunction "G_4") (pintype "bidirectional"))
      (node (ref "TG1") (pin "1") (pinfunction "1_1") (pintype "passive"))
    )
    (net (code "53") (name "Net-(M2-S_1)") (class "Default")
      (node (ref "M2") (pin "1") (pinfunction "S_1_1") (pintype "bidirectional"))
      (node (ref "M2") (pin "2") (pinfunction "S_2_2") (pintype "bidirectional"))
      (node (ref "M2") (pin "3") (pinfunction "S_3_3") (pintype "bidirectional"))
      (node (ref "M3") (pin "1") (pinfunction "S_1_1") (pintype "bidirectional"))
      (node (ref "M3") (pin "2") (pinfunction "S_2_2") (pintype "bidirectional"))
      (node (ref "M3") (pin "3") (pinfunction "S_3_3") (pintype "bidirectional"))
      (node (ref "TG2") (pin "2") (pinfunction "2_2") (pintype "passive"))
      (node (ref "TG3") (pin "1") (pinfunction "1_1") (pintype "bidirectional"))
    )
    (net (code "54") (name "Net-(M3-G)") (class "Default")
      (node (ref "M3") (pin "4") (pinfunction "G_4") (pintype "bidirectional"))
      (node (ref "TG5") (pin "1") (pinfunction "1_1") (pintype "passive"))
    )
    (net (code "55") (name "unconnected-(ARDUINO_NANO1-3V3-Pad2)") (class "Default")
      (node (ref "ARDUINO_NANO1") (pin "2") (pinfunction "3V3_2") (pintype "output"))
    )
    (net (code "56") (name "unconnected-(ARDUINO_NANO1-A1-Pad5)") (class "Default")
      (node (ref "ARDUINO_NANO1") (pin "5") (pinfunction "A1_5") (pintype "bidirectional"))
    )
    (net (code "57") (name "unconnected-(ARDUINO_NANO1-A2-Pad6)") (class "Default")
      (node (ref "ARDUINO_NANO1") (pin "6") (pinfunction "A2_6") (pintype "bidirectional"))
    )
    (net (code "58") (name "unconnected-(ARDUINO_NANO1-A3-Pad7)") (class "Default")
      (node (ref "ARDUINO_NANO1") (pin "7") (pinfunction "A3_7") (pintype "bidirectional"))
    )
    (net (code "59") (name "unconnected-(ARDUINO_NANO1-A6-Pad10)") (class "Default")
      (node (ref "ARDUINO_NANO1") (pin "10") (pinfunction "A6_10") (pintype "bidirectional"))
    )
    (net (code "60") (name "unconnected-(ARDUINO_NANO1-A7-Pad11)") (class "Default")
      (node (ref "ARDUINO_NANO1") (pin "11") (pinfunction "A7_11") (pintype "bidirectional"))
    )
    (net (code "61") (name "unconnected-(ARDUINO_NANO1-AREF-Pad3)") (class "Default")
      (node (ref "ARDUINO_NANO1") (pin "3") (pinfunction "AREF_3") (pintype "input"))
    )
    (net (code "62") (name "unconnected-(ARDUINO_NANO1-D2-Pad20)") (class "Default")
      (node (ref "ARDUINO_NANO1") (pin "20") (pinfunction "D2_20") (pintype "bidirectional"))
    )
    (net (code "63") (name "unconnected-(ARDUINO_NANO1-D4-Pad22)") (class "Default")
      (node (ref "ARDUINO_NANO1") (pin "22") (pinfunction "D4_22") (pintype "bidirectional"))
    )
    (net (code "64") (name "unconnected-(ARDUINO_NANO1-D5-Pad23)") (class "Default")
      (node (ref "ARDUINO_NANO1") (pin "23") (pinfunction "D5_23") (pintype "bidirectional"))
    )
    (net (code "65") (name "unconnected-(ARDUINO_NANO1-D6-Pad24)") (class "Default")
      (node (ref "ARDUINO_NANO1") (pin "24") (pinfunction "D6_24") (pintype "bidirectional"))
    )
    (net (code "66") (name "unconnected-(ARDUINO_NANO1-D7-Pad25)") (class "Default")
      (node (ref "ARDUINO_NANO1") (pin "25") (pinfunction "D7_25") (pintype "bidirectional"))
    )
    (net (code "67") (name "unconnected-(ARDUINO_NANO1-D8-Pad26)") (class "Default")
      (node (ref "ARDUINO_NANO1") (pin "26") (pinfunction "D8_26") (pintype "bidirectional"))
    )
    (net (code "68") (name "unconnected-(ARDUINO_NANO1-D9-Pad27)") (class "Default")
      (node (ref "ARDUINO_NANO1") (pin "27") (pinfunction "D9_27") (pintype "bidirectional"))
    )
    (net (code "69") (name "unconnected-(ARDUINO_NANO1-D10-Pad28)") (class "Default")
      (node (ref "ARDUINO_NANO1") (pin "28") (pinfunction "D10_28") (pintype "bidirectional"))
    )
    (net (code "70") (name "unconnected-(ARDUINO_NANO1-D11-Pad29)") (class "Default")
      (node (ref "ARDUINO_NANO1") (pin "29") (pinfunction "D11_29") (pintype "bidirectional"))
    )
    (net (code "71") (name "unconnected-(ARDUINO_NANO1-D12-Pad30)") (class "Default")
      (node (ref "ARDUINO_NANO1") (pin "30") (pinfunction "D12_30") (pintype "bidirectional"))
    )
    (net (code "72") (name "unconnected-(ARDUINO_NANO1-D13-Pad1)") (class "Default")
      (node (ref "ARDUINO_NANO1") (pin "1") (pinfunction "D13_1") (pintype "bidirectional"))
    )
    (net (code "73") (name "unconnected-(ARDUINO_NANO1-RX0-Pad17)") (class "Default")
      (node (ref "ARDUINO_NANO1") (pin "17") (pinfunction "RX0_17") (pintype "bidirectional"))
    )
    (net (code "74") (name "unconnected-(ARDUINO_NANO1-TX1-Pad16)") (class "Default")
      (node (ref "ARDUINO_NANO1") (pin "16") (pinfunction "TX1_16") (pintype "bidirectional"))
    )
    (net (code "75") (name "unconnected-(ARDUINO_NANO1-~{RESET}-Pad13)") (class "Default")
      (node (ref "ARDUINO_NANO1") (pin "13") (pinfunction "~{RESET}_13") (pintype "input"))
    )
    (net (code "76") (name "unconnected-(ARDUINO_NANO1-~{RESET}-Pad18)") (class "Default")
      (node (ref "ARDUINO_NANO1") (pin "18") (pinfunction "~{RESET}_18") (pintype "input"))
    )
    (net (code "77") (name "unconnected-(U1-ECON-Pad48)") (class "Default")
      (node (ref "U1") (pin "48") (pinfunction "ECON_48") (pintype "passive"))
    )
    (net (code "78") (name "unconnected-(U1-NC-Pad60)") (class "Default")
      (node (ref "U1") (pin "60") (pinfunction "NC_60") (pintype "passive"))
    )
    (net (code "79") (name "unconnected-(U1-NC_2-Pad52)") (class "Default")
      (node (ref "U1") (pin "52") (pinfunction "NC_2_52") (pintype "passive"))
    )
    (net (code "80") (name "unconnected-(U1-SRVO_FBIN-Pad35)") (class "Default")
      (node (ref "U1") (pin "35") (pinfunction "SRVO_FBIN_35") (pintype "passive"))
    )
    (net (code "81") (name "unconnected-(U1-SRVO_FBOUT-Pad38)") (class "Default")
      (node (ref "U1") (pin "38") (pinfunction "SRVO_FBOUT_38") (pintype "passive"))
    )
    (net (code "82") (name "unconnected-(U1-SRVO_IIN-Pad36)") (class "Default")
      (node (ref "U1") (pin "36") (pinfunction "SRVO_IIN_36") (pintype "passive"))
    )
    (net (code "83") (name "unconnected-(U1-SRVO_IOUT-Pad37)") (class "Default")
      (node (ref "U1") (pin "37") (pinfunction "SRVO_IOUT_37") (pintype "passive"))
    )
  )
)
